# Sheet1.net
KiCad netlist of a schematic drawn in Altium Designer
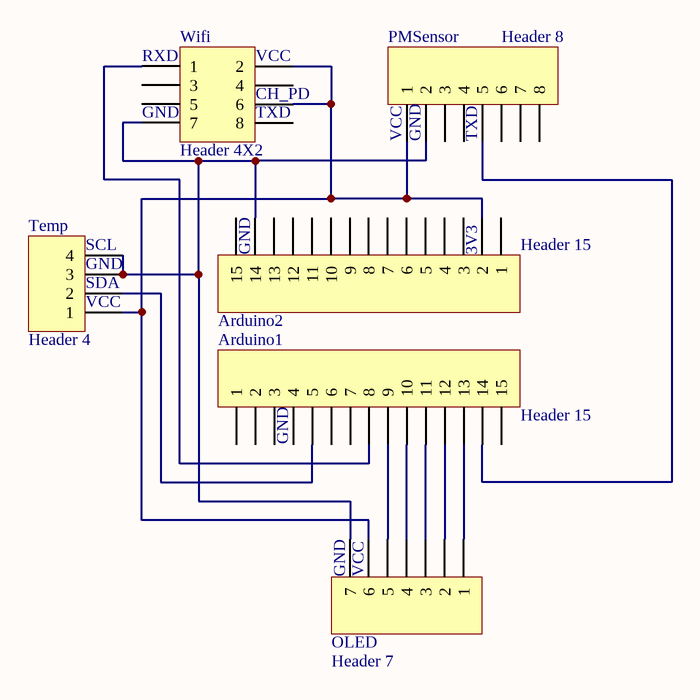
[diagram p0: Sheet1.SchDoc]

(export (version "E")
  (design (tool "Eeschema 10.0.6"))
  (components
    (comp (ref "Arduino1")
      (value "Header 15")
      (footprint "HDR1X15")
      (description "Header, 15-Pin")
      (fields (field (name "PUBLISHER") "Altium Limited"))
      (libsource (lib "") (part "Header 15_1"))
    )
    (comp (ref "Arduino2")
      (value "Header 15")
      (footprint "HDR1X15")
      (description "Header, 15-Pin")
      (fields (field (name "PUBLISHER") "Altium Limited"))
      (libsource (lib "Miscellaneous Connectors") (part "Header 15"))
    )
    (comp (ref "OLED")
      (value "Header 7")
      (footprint "HDR1X7")
      (description "Header, 7-Pin")
      (fields (field (name "PUBLISHER") "Altium Limited"))
      (libsource (lib "Miscellaneous Connectors") (part "Header 7"))
    )
    (comp (ref "PMSensor")
      (value "Header 8")
      (footprint "HDR1X8")
      (description "Header, 8-Pin")
      (fields (field (name "PUBLISHER") "Altium Limited"))
      (libsource (lib "Miscellaneous Connectors") (part "Header 8"))
    )
    (comp (ref "Temp")
      (value "Header 4")
      (footprint "HDR1X4")
      (description "Header, 4-Pin")
      (fields (field (name "PUBLISHER") "Altium Limited"))
      (libsource (lib "Miscellaneous Connectors") (part "Header 4"))
    )
    (comp (ref "Wifi")
      (value "Header 4X2")
      (footprint "HDR2X4")
      (description "Header, 4-Pin, Dual row")
      (fields (field (name "PUBLISHER") "Altium Limited"))
      (libsource (lib "Miscellaneous Connectors") (part "Header 4X2"))
    )
  )
  (nets
    (net (code "1") (name "Net-(Arduino1-Pad5)") (class "Default")
      (node (ref "Arduino1") (pin "5") (pinfunction "5_5") (pintype "passive"))
      (node (ref "Temp") (pin "2") (pinfunction "2_2") (pintype "passive"))
    )
    (net (code "2") (name "Net-(Arduino1-Pad8)") (class "Default")
      (node (ref "Arduino1") (pin "8") (pinfunction "8_8") (pintype "passive"))
      (node (ref "Wifi") (pin "1") (pinfunction "1_1") (pintype "passive"))
    )
    (net (code "3") (name "Net-(Arduino1-Pad9)") (class "Default")
      (node (ref "Arduino1") (pin "9") (pinfunction "9_9") (pintype "passive"))
      (node (ref "OLED") (pin "5") (pinfunction "5_5") (pintype "passive"))
    )
    (net (code "4") (name "Net-(Arduino1-Pad10)") (class "Default")
      (node (ref "Arduino1") (pin "10") (pinfunction "10_10") (pintype "passive"))
      (node (ref "OLED") (pin "4") (pinfunction "4_4") (pintype "passive"))
    )
    (net (code "5") (name "Net-(Arduino1-Pad11)") (class "Default")
      (node (ref "Arduino1") (pin "11") (pinfunction "11_11") (pintype "passive"))
      (node (ref "OLED") (pin "3") (pinfunction "3_3") (pintype "passive"))
    )
    (net (code "6") (name "Net-(Arduino1-Pad12)") (class "Default")
      (node (ref "Arduino1") (pin "12") (pinfunction "12_12") (pintype "passive"))
      (node (ref "OLED") (pin "2") (pinfunction "2_2") (pintype "passive"))
    )
    (net (code "7") (name "Net-(Arduino1-Pad13)") (class "Default")
      (node (ref "Arduino1") (pin "13") (pinfunction "13_13") (pintype "passive"))
      (node (ref "OLED") (pin "1") (pinfunction "1_1") (pintype "passive"))
    )
    (net (code "8") (name "Net-(Arduino1-Pad14)") (class "Default")
      (node (ref "Arduino1") (pin "14") (pinfunction "14_14") (pintype "passive"))
      (node (ref "PMSensor") (pin "5") (pinfunction "5_5") (pintype "passive"))
    )
    (net (code "9") (name "Net-(Arduino2-Pad2)") (class "Default")
      (node (ref "Arduino2") (pin "2") (pinfunction "2_2") (pintype "passive"))
      (node (ref "OLED") (pin "6") (pinfunction "6_6") (pintype "passive"))
      (node (ref "PMSensor") (pin "1") (pinfunction "1_1") (pintype "passive"))
      (node (ref "Temp") (pin "1") (pinfunction "1_1") (pintype "passive"))
      (node (ref "Wifi") (pin "2") (pinfunction "2_2") (pintype "passive"))
      (node (ref "Wifi") (pin "6") (pinfunction "6_6") (pintype "passive"))
    )
    (net (code "10") (name "Net-(Arduino2-Pad14)") (class "Default")
      (node (ref "Arduino2") (pin "14") (pinfunction "14_14") (pintype "passive"))
      (node (ref "OLED") (pin "7") (pinfunction "7_7") (pintype "passive"))
      (node (ref "PMSensor") (pin "2") (pinfunction "2_2") (pintype "passive"))
      (node (ref "Temp") (pin "3") (pinfunction "3_3") (pintype "passive"))
      (node (ref "Temp") (pin "4") (pinfunction "4_4") (pintype "passive"))
      (node (ref "Wifi") (pin "7") (pinfunction "7_7") (pintype "passive"))
    )
    (net (code "11") (name "unconnected-(Arduino1-Pad1)") (class "Default")
      (node (ref "Arduino1") (pin "1") (pinfunction "1_1") (pintype "passive"))
    )
    (net (code "12") (name "unconnected-(Arduino1-Pad2)") (class "Default")
      (node (ref "Arduino1") (pin "2") (pinfunction "2_2") (pintype "passive"))
    )
    (net (code "13") (name "unconnected-(Arduino1-Pad3)") (class "Default")
      (node (ref "Arduino1") (pin "3") (pinfunction "3_3") (pintype "passive"))
    )
    (net (code "14") (name "unconnected-(Arduino1-Pad4)") (class "Default")
      (node (ref "Arduino1") (pin "4") (pinfunction "4_4") (pintype "passive"))
    )
    (net (code "15") (name "unconnected-(Arduino1-Pad6)") (class "Default")
      (node (ref "Arduino1") (pin "6") (pinfunction "6_6") (pintype "passive"))
    )
    (net (code "16") (name "unconnected-(Arduino1-Pad7)") (class "Default")
      (node (ref "Arduino1") (pin "7") (pinfunction "7_7") (pintype "passive"))
    )
    (net (code "17") (name "unconnected-(Arduino1-Pad15)") (class "Default")
      (node (ref "Arduino1") (pin "15") (pinfunction "15_15") (pintype "passive"))
    )
    (net (code "18") (name "unconnected-(Arduino2-Pad1)") (class "Default")
      (node (ref "Arduino2") (pin "1") (pinfunction "1_1") (pintype "passive"))
    )
    (net (code "19") (name "unconnected-(Arduino2-Pad3)") (class "Default")
      (node (ref "Arduino2") (pin "3") (pinfunction "3_3") (pintype "passive"))
    )
    (net (code "20") (name "unconnected-(Arduino2-Pad4)") (class "Default")
      (node (ref "Arduino2") (pin "4") (pinfunction "4_4") (pintype "passive"))
    )
    (net (code "21") (name "unconnected-(Arduino2-Pad5)") (class "Default")
      (node (ref "Arduino2") (pin "5") (pinfunction "5_5") (pintype "passive"))
    )
    (net (code "22") (name "unconnected-(Arduino2-Pad6)") (class "Default")
      (node (ref "Arduino2") (pin "6") (pinfunction "6_6") (pintype "passive"))
    )
    (net (code "23") (name "unconnected-(Arduino2-Pad7)") (class "Default")
      (node (ref "Arduino2") (pin "7") (pinfunction "7_7") (pintype "passive"))
    )
    (net (code "24") (name "unconnected-(Arduino2-Pad8)") (class "Default")
      (node (ref "Arduino2") (pin "8") (pinfunction "8_8") (pintype "passive"))
    )
    (net (code "25") (name "unconnected-(Arduino2-Pad9)") (class "Default")
      (node (ref "Arduino2") (pin "9") (pinfunction "9_9") (pintype "passive"))
    )
    (net (code "26") (name "unconnected-(Arduino2-Pad10)") (class "Default")
      (node (ref "Arduino2") (pin "10") (pinfunction "10_10") (pintype "passive"))
    )
    (net (code "27") (name "unconnected-(Arduino2-Pad11)") (class "Default")
      (node (ref "Arduino2") (pin "11") (pinfunction "11_11") (pintype "passive"))
    )
    (net (code "28") (name "unconnected-(Arduino2-Pad12)") (class "Default")
      (node (ref "Arduino2") (pin "12") (pinfunction "12_12") (pintype "passive"))
    )
    (net (code "29") (name "unconnected-(Arduino2-Pad13)") (class "Default")
      (node (ref "Arduino2") (pin "13") (pinfunction "13_13") (pintype "passive"))
    )
    (net (code "30") (name "unconnected-(Arduino2-Pad15)") (class "Default")
      (node (ref "Arduino2") (pin "15") (pinfunction "15_15") (pintype "passive"))
    )
    (net (code "31") (name "unconnected-(PMSensor-Pad3)") (class "Default")
      (node (ref "PMSensor") (pin "3") (pinfunction "3_3") (pintype "passive"))
    )
    (net (code "32") (name "unconnected-(PMSensor-Pad4)") (class "Default")
      (node (ref "PMSensor") (pin "4") (pinfunction "4_4") (pintype "passive"))
    )
    (net (code "33") (name "unconnected-(PMSensor-Pad6)") (class "Default")
      (node (ref "PMSensor") (pin "6") (pinfunction "6_6") (pintype "passive"))
    )
    (net (code "34") (name "unconnected-(PMSensor-Pad7)") (class "Default")
      (node (ref "PMSensor") (pin "7") (pinfunction "7_7") (pintype "passive"))
    )
    (net (code "35") (name "unconnected-(PMSensor-Pad8)") (class "Default")
      (node (ref "PMSensor") (pin "8") (pinfunction "8_8") (pintype "passive"))
    )
    (net (code "36") (name "unconnected-(Wifi-Pad3)") (class "Default")
      (node (ref "Wifi") (pin "3") (pinfunction "3_3") (pintype "passive"))
    )
    (net (code "37") (name "unconnected-(Wifi-Pad4)") (class "Default")
      (node (ref "Wifi") (pin "4") (pinfunction "4_4") (pintype "passive"))
    )
    (net (code "38") (name "unconnected-(Wifi-Pad5)") (class "Default")
      (node (ref "Wifi") (pin "5") (pinfunction "5_5") (pintype "passive"))
    )
    (net (code "39") (name "unconnected-(Wifi-Pad8)") (class "Default")
      (node (ref "Wifi") (pin "8") (pinfunction "8_8") (pintype "passive"))
    )
  )
)
